# Driver.net
KiCad netlist of a schematic drawn in Altium Designer
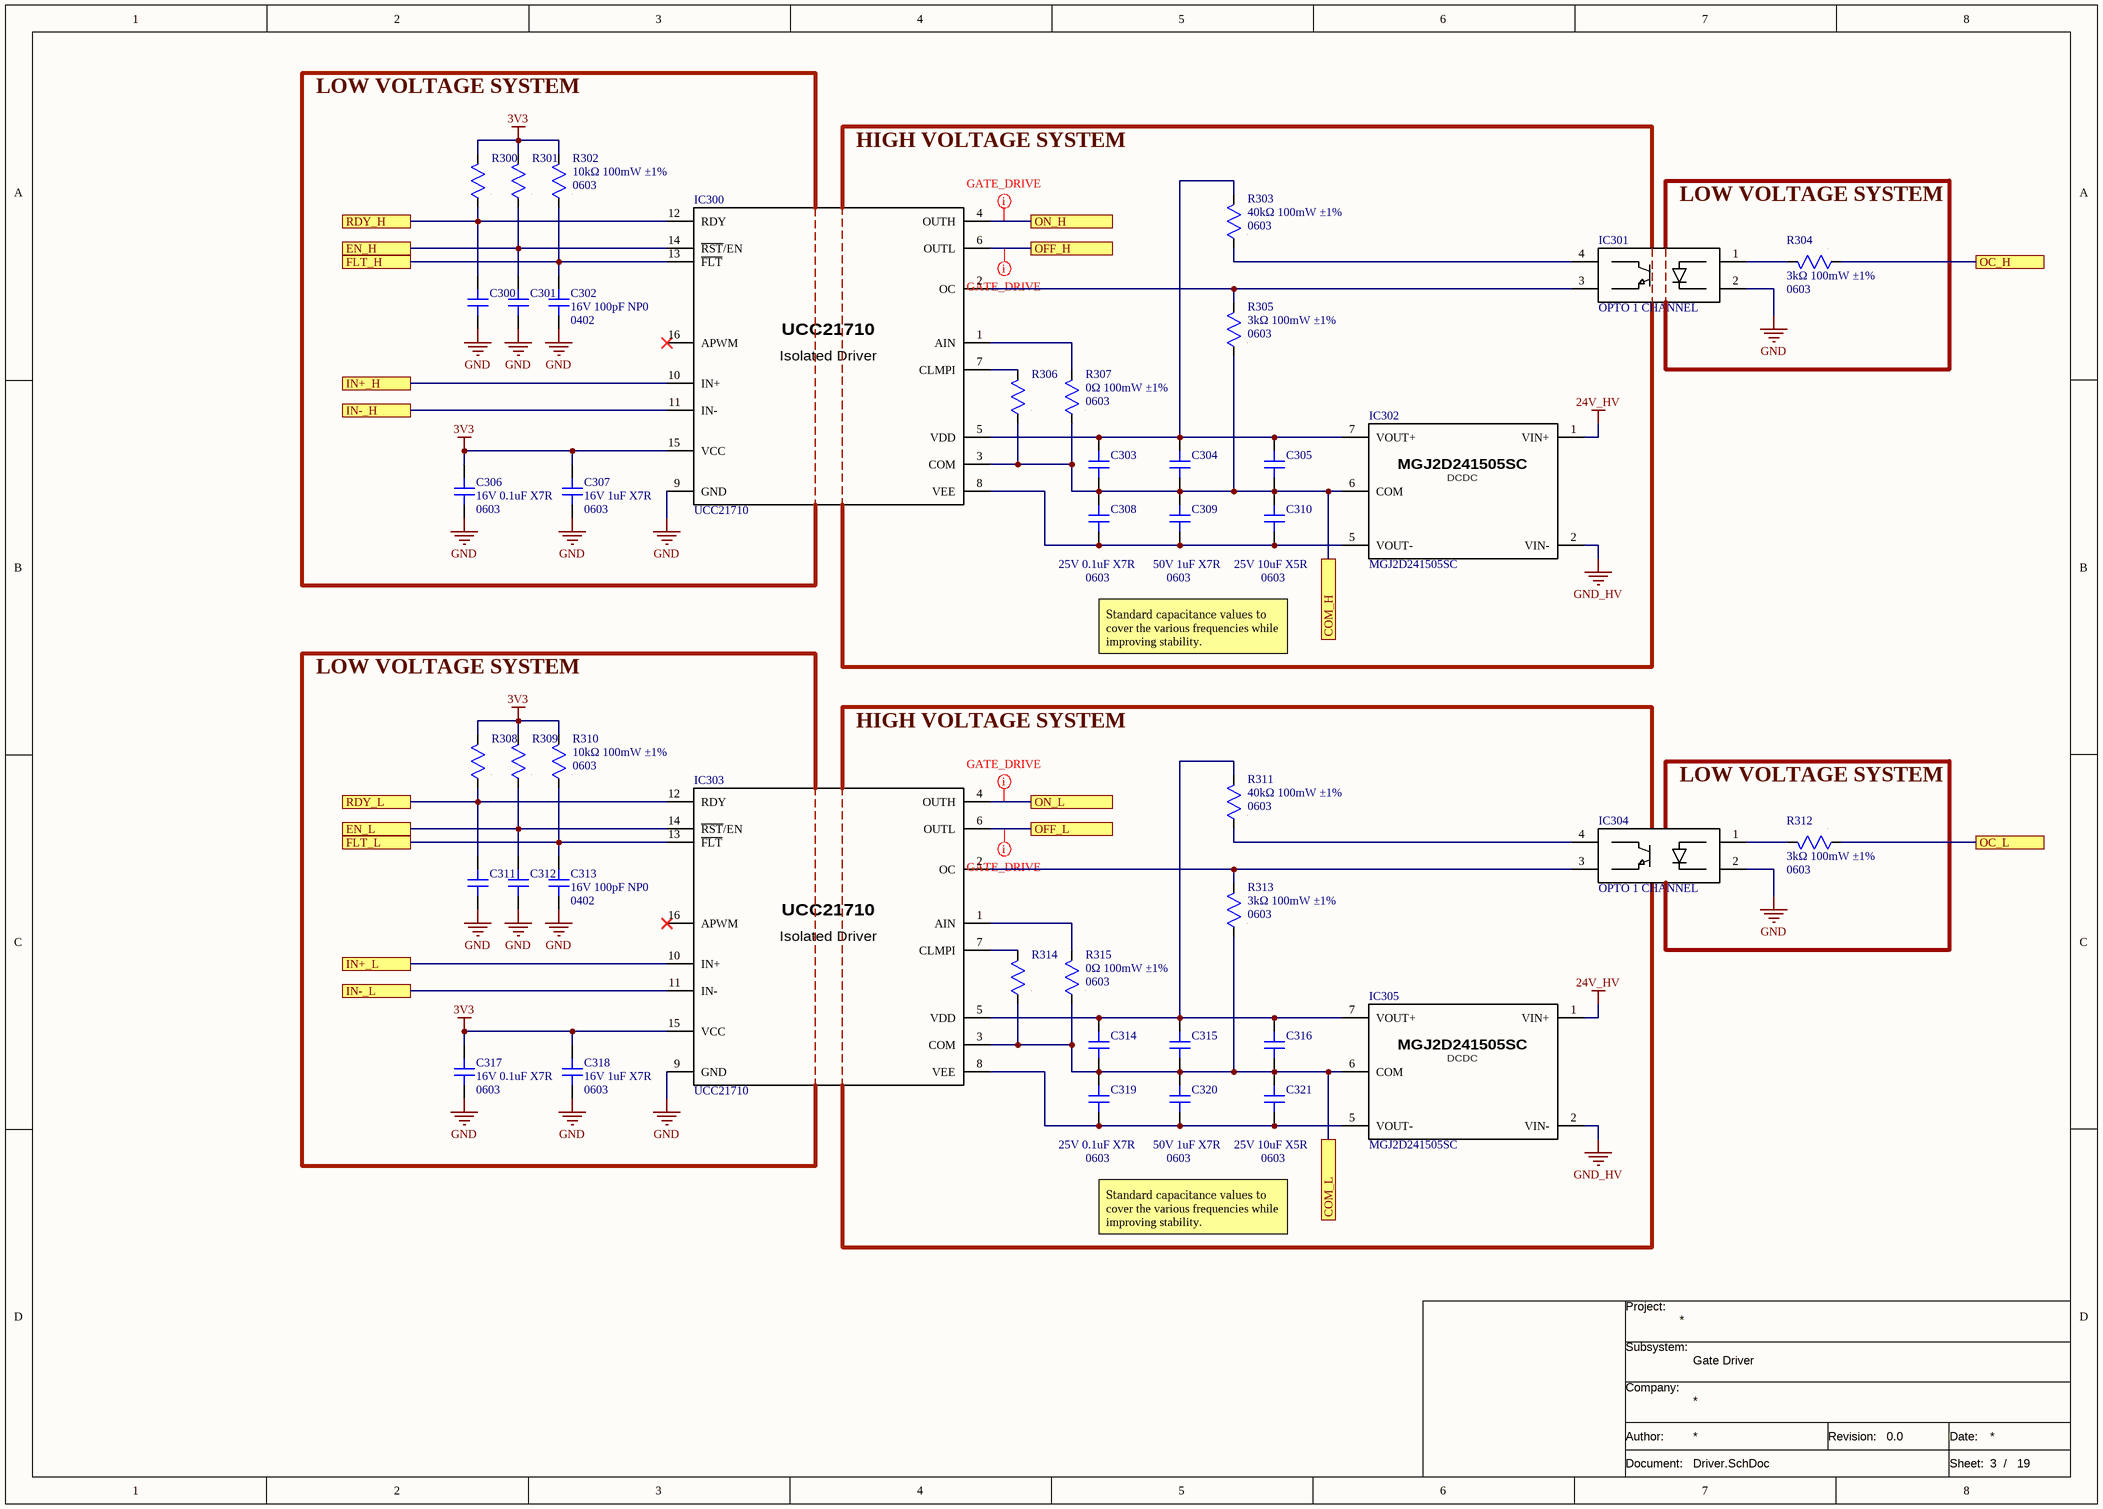
[diagram p0: Driver.SchDoc]

(export (version "E")
  (design (tool "Eeschema 10.0.6"))
  (components
    (comp (ref "C300")
      (value "CAP non polarized")
      (footprint "CAP SMD 0402")
      (description "Condensadores de cerámica multicapa (MLCC- SMD/SMT) WCAP-CSGP 100pF 0402 5% 16V MLCC")
      (fields (field (name "MPN") "885012005031") (field (name "MANUFACTURER") "Wurth Elektronik"))
      (libsource (lib "eUSR_Database") (part "CAP non polarized"))
    )
    (comp (ref "C301")
      (value "CAP non polarized")
      (footprint "CAP SMD 0402")
      (description "Condensadores de cerámica multicapa (MLCC- SMD/SMT) WCAP-CSGP 100pF 0402 5% 16V MLCC")
      (fields (field (name "MPN") "885012005031") (field (name "MANUFACTURER") "Wurth Elektronik"))
      (libsource (lib "eUSR_Database") (part "CAP non polarized"))
    )
    (comp (ref "C302")
      (value "16V 100pF NP0")
      (footprint "CAP SMD 0402")
      (description "Condensadores de cerámica multicapa (MLCC- SMD/SMT) WCAP-CSGP 100pF 0402 5% 16V MLCC")
      (fields
        (field (name "PACKAGE") "0402")
        (field (name "MPN") "885012005031")
        (field (name "MANUFACTURER") "Wurth Elektronik")
      )
      (libsource (lib "eUSR_Database") (part "CAP non polarized"))
    )
    (comp (ref "C303")
      (value "CAP non polarized")
      (footprint "CAP SMD 0603")
      (description "Condensadores de cerámica multicapa (MLCC- SMD/SMT) WCAP-CSGP 0.1uF 0603 10% 25V MLCC")
      (fields (field (name "MPN") "885012206071") (field (name "MANUFACTURER") "Wurth Elektronik"))
      (libsource (lib "eUSR_Database") (part "CAP non polarized"))
    )
    (comp (ref "C304")
      (value "CAP non polarized")
      (footprint "CAP SMD 0603")
      (description "Condensadores de cerámica multicapa (MLCC- SMD/SMT) WCAP-CSGP 1uF 50 Vol 10%")
      (fields (field (name "MPN") "885012206126") (field (name "MANUFACTURER") "Wurth Elektronik"))
      (libsource (lib "eUSR_Database") (part "CAP non polarized"))
    )
    (comp (ref "C305")
      (value "CAP non polarized")
      (footprint "CAP SMD 0603")
      (description "Condensadores de cerámica multicapa (MLCC- SMD/SMT) 0603 25VDC 10uF 10% X5R")
      (fields (field (name "MPN") "ZRB18AR61E106KE01L") (field (name "MANUFACTURER") "muRata"))
      (libsource (lib "eUSR_Database") (part "CAP non polarized"))
    )
    (comp (ref "C306")
      (value "16V 0.1uF X7R")
      (footprint "CAP SMD 0603")
      (description "Condensadores de cerámica multicapa (MLCC- SMD/SMT) WCAP-CSGP 0.1uF 0603 10% 16V MLCC")
      (fields
        (field (name "PACKAGE") "0603")
        (field (name "MPN") "885012206046")
        (field (name "MANUFACTURER") "Wurth Elektronik")
      )
      (libsource (lib "eUSR_Database") (part "CAP non polarized"))
    )
    (comp (ref "C307")
      (value "16V 1uF X7R")
      (footprint "CAP SMD 0603")
      (description "Condensadores de cerámica multicapa (MLCC- SMD/SMT) WCAP-CSGP 1uF 0603 10% 16V MLCC")
      (fields
        (field (name "PACKAGE") "0603")
        (field (name "MPN") "885012206052")
        (field (name "MANUFACTURER") "Wurth Elektronik")
      )
      (libsource (lib "eUSR_Database") (part "CAP non polarized"))
    )
    (comp (ref "C308")
      (value "25V 0.1uF X7R")
      (footprint "CAP SMD 0603")
      (description "Condensadores de cerámica multicapa (MLCC- SMD/SMT) WCAP-CSGP 0.1uF 0603 10% 25V MLCC")
      (fields
        (field (name "PACKAGE") "0603")
        (field (name "MPN") "885012206071")
        (field (name "MANUFACTURER") "Wurth Elektronik")
      )
      (libsource (lib "eUSR_Database") (part "CAP non polarized"))
    )
    (comp (ref "C309")
      (value "50V 1uF X7R")
      (footprint "CAP SMD 0603")
      (description "Condensadores de cerámica multicapa (MLCC- SMD/SMT) WCAP-CSGP 1uF 50 Vol 10%")
      (fields
        (field (name "PACKAGE") "0603")
        (field (name "MPN") "885012206126")
        (field (name "MANUFACTURER") "Wurth Elektronik")
      )
      (libsource (lib "eUSR_Database") (part "CAP non polarized"))
    )
    (comp (ref "C310")
      (value "25V 10uF X5R")
      (footprint "CAP SMD 0603")
      (description "Condensadores de cerámica multicapa (MLCC- SMD/SMT) 0603 25VDC 10uF 10% X5R")
      (fields
        (field (name "PACKAGE") "0603")
        (field (name "MPN") "ZRB18AR61E106KE01L")
        (field (name "MANUFACTURER") "muRata")
      )
      (libsource (lib "eUSR_Database") (part "CAP non polarized"))
    )
    (comp (ref "C311")
      (value "CAP non polarized")
      (footprint "CAP SMD 0402")
      (description "Condensadores de cerámica multicapa (MLCC- SMD/SMT) WCAP-CSGP 100pF 0402 5% 16V MLCC")
      (fields (field (name "MPN") "885012005031") (field (name "MANUFACTURER") "Wurth Elektronik"))
      (libsource (lib "eUSR_Database") (part "CAP non polarized"))
    )
    (comp (ref "C312")
      (value "CAP non polarized")
      (footprint "CAP SMD 0402")
      (description "Condensadores de cerámica multicapa (MLCC- SMD/SMT) WCAP-CSGP 100pF 0402 5% 16V MLCC")
      (fields (field (name "MPN") "885012005031") (field (name "MANUFACTURER") "Wurth Elektronik"))
      (libsource (lib "eUSR_Database") (part "CAP non polarized"))
    )
    (comp (ref "C313")
      (value "16V 100pF NP0")
      (footprint "CAP SMD 0402")
      (description "Condensadores de cerámica multicapa (MLCC- SMD/SMT) WCAP-CSGP 100pF 0402 5% 16V MLCC")
      (fields
        (field (name "PACKAGE") "0402")
        (field (name "MPN") "885012005031")
        (field (name "MANUFACTURER") "Wurth Elektronik")
      )
      (libsource (lib "eUSR_Database") (part "CAP non polarized"))
    )
    (comp (ref "C314")
      (value "CAP non polarized")
      (footprint "CAP SMD 0603")
      (description "Condensadores de cerámica multicapa (MLCC- SMD/SMT) WCAP-CSGP 0.1uF 0603 10% 25V MLCC")
      (fields (field (name "MPN") "885012206071") (field (name "MANUFACTURER") "Wurth Elektronik"))
      (libsource (lib "eUSR_Database") (part "CAP non polarized"))
    )
    (comp (ref "C315")
      (value "CAP non polarized")
      (footprint "CAP SMD 0603")
      (description "Condensadores de cerámica multicapa (MLCC- SMD/SMT) WCAP-CSGP 1uF 50 Vol 10%")
      (fields (field (name "MPN") "885012206126") (field (name "MANUFACTURER") "Wurth Elektronik"))
      (libsource (lib "eUSR_Database") (part "CAP non polarized"))
    )
    (comp (ref "C316")
      (value "CAP non polarized")
      (footprint "CAP SMD 0603")
      (description "Condensadores de cerámica multicapa (MLCC- SMD/SMT) 0603 25VDC 10uF 10% X5R")
      (fields (field (name "MPN") "ZRB18AR61E106KE01L") (field (name "MANUFACTURER") "muRata"))
      (libsource (lib "eUSR_Database") (part "CAP non polarized"))
    )
    (comp (ref "C317")
      (value "16V 0.1uF X7R")
      (footprint "CAP SMD 0603")
      (description "Condensadores de cerámica multicapa (MLCC- SMD/SMT) WCAP-CSGP 0.1uF 0603 10% 16V MLCC")
      (fields
        (field (name "PACKAGE") "0603")
        (field (name "MPN") "885012206046")
        (field (name "MANUFACTURER") "Wurth Elektronik")
      )
      (libsource (lib "eUSR_Database") (part "CAP non polarized"))
    )
    (comp (ref "C318")
      (value "16V 1uF X7R")
      (footprint "CAP SMD 0603")
      (description "Condensadores de cerámica multicapa (MLCC- SMD/SMT) WCAP-CSGP 1uF 0603 10% 16V MLCC")
      (fields
        (field (name "PACKAGE") "0603")
        (field (name "MPN") "885012206052")
        (field (name "MANUFACTURER") "Wurth Elektronik")
      )
      (libsource (lib "eUSR_Database") (part "CAP non polarized"))
    )
    (comp (ref "C319")
      (value "25V 0.1uF X7R")
      (footprint "CAP SMD 0603")
      (description "Condensadores de cerámica multicapa (MLCC- SMD/SMT) WCAP-CSGP 0.1uF 0603 10% 25V MLCC")
      (fields
        (field (name "PACKAGE") "0603")
        (field (name "MPN") "885012206071")
        (field (name "MANUFACTURER") "Wurth Elektronik")
      )
      (libsource (lib "eUSR_Database") (part "CAP non polarized"))
    )
    (comp (ref "C320")
      (value "50V 1uF X7R")
      (footprint "CAP SMD 0603")
      (description "Condensadores de cerámica multicapa (MLCC- SMD/SMT) WCAP-CSGP 1uF 50 Vol 10%")
      (fields
        (field (name "PACKAGE") "0603")
        (field (name "MPN") "885012206126")
        (field (name "MANUFACTURER") "Wurth Elektronik")
      )
      (libsource (lib "eUSR_Database") (part "CAP non polarized"))
    )
    (comp (ref "C321")
      (value "25V 10uF X5R")
      (footprint "CAP SMD 0603")
      (description "Condensadores de cerámica multicapa (MLCC- SMD/SMT) 0603 25VDC 10uF 10% X5R")
      (fields
        (field (name "PACKAGE") "0603")
        (field (name "MPN") "ZRB18AR61E106KE01L")
        (field (name "MANUFACTURER") "muRata")
      )
      (libsource (lib "eUSR_Database") (part "CAP non polarized"))
    )
    (comp (ref "IC300")
      (value "UCC21710")
      (footprint "SOIC-16")
      (fields (field (name "MPN") "UCC21710QDWRQ1") (field (name "MANUFACTURER") "Texas Instruments"))
      (libsource (lib "eUSR_Database") (part "UCC21710"))
    )
    (comp (ref "IC301")
      (value "OPTO 1 CHANNEL")
      (footprint "SOIC-4")
      (description "Optoacopladores para salidas de transistores Automotive DC-input transistor-output s")
      (fields (field (name "MPN") "ISOM8110DFHRQ1") (field (name "MANUFACTURER") "Texas Instruments"))
      (libsource (lib "eUSR_Database") (part "OPTO 1 CHANNEL"))
    )
    (comp (ref "IC302")
      (value "MGJ2D241505SC")
      (footprint "MGJ2D241505SC")
      (description "Convertidores DC/DC para montaje pasante 2W 24-15VIN 5VOUT DC/DC")
      (fields (field (name "MANUFACTURER") "Murata Power Solutions"))
      (libsource (lib "eUSR_Database") (part "MGJ2D241505SC"))
    )
    (comp (ref "IC303")
      (value "UCC21710")
      (footprint "SOIC-16")
      (fields (field (name "MPN") "UCC21710QDWRQ1") (field (name "MANUFACTURER") "Texas Instruments"))
      (libsource (lib "eUSR_Database") (part "UCC21710"))
    )
    (comp (ref "IC304")
      (value "OPTO 1 CHANNEL")
      (footprint "SOIC-4")
      (description "Optoacopladores para salidas de transistores Automotive DC-input transistor-output s")
      (fields (field (name "MPN") "ISOM8110DFHRQ1") (field (name "MANUFACTURER") "Texas Instruments"))
      (libsource (lib "eUSR_Database") (part "OPTO 1 CHANNEL"))
    )
    (comp (ref "IC305")
      (value "MGJ2D241505SC")
      (footprint "MGJ2D241505SC")
      (description "Convertidores DC/DC para montaje pasante 2W 24-15VIN 5VOUT DC/DC")
      (fields (field (name "MANUFACTURER") "Murata Power Solutions"))
      (libsource (lib "eUSR_Database") (part "MGJ2D241505SC"))
    )
    (comp (ref "R300")
      (value "RES")
      (footprint "RES SMD 0603")
      (description "Resistores de película gruesa - SMD WRIS-RSKS 10 kOhms 1 % 0.1 W 0603 AEC-Q200")
      (fields (field (name "MPN") "560112116005") (field (name "MANUFACTURER") "Wurth Elektronik"))
      (libsource (lib "eUSR_Database") (part "RES"))
    )
    (comp (ref "R301")
      (value "RES")
      (footprint "RES SMD 0603")
      (description "Resistores de película gruesa - SMD WRIS-RSKS 10 kOhms 1 % 0.1 W 0603 AEC-Q200")
      (fields (field (name "MPN") "560112116005") (field (name "MANUFACTURER") "Wurth Elektronik"))
      (libsource (lib "eUSR_Database") (part "RES"))
    )
    (comp (ref "R302")
      (value "10kΩ 100mW ±1%")
      (footprint "RES SMD 0603")
      (description "Resistores de película gruesa - SMD WRIS-RSKS 10 kOhms 1 % 0.1 W 0603 AEC-Q200")
      (fields
        (field (name "PACKAGE") "0603")
        (field (name "MPN") "560112116005")
        (field (name "MANUFACTURER") "Wurth Elektronik")
      )
      (libsource (lib "eUSR_Database") (part "RES"))
    )
    (comp (ref "R303")
      (value "40kΩ 100mW ±1%")
      (footprint "RES SMD 0603")
      (description "Thin Film Resistors 40kOhm 1/10W 0603 .1 %")
      (fields
        (field (name "PACKAGE") "0603")
        (field (name "MPN") "RT0603BRD0740KL")
        (field (name "MANUFACTURER") "YAGEO")
      )
      (libsource (lib "eUSR_Database") (part "RES"))
    )
    (comp (ref "R304")
      (value "3kΩ 100mW ±1%")
      (footprint "RES SMD 0603")
      (description "Thin Film Resistors .1W 3Kohm 1% 0603 50ppm Auto")
      (fields
        (field (name "PACKAGE") "0603")
        (field (name "MPN") "MCT06030C3001FP500")
        (field (name "MANUFACTURER") "Vishay")
      )
      (libsource (lib "eUSR_Database") (part "RES"))
    )
    (comp (ref "R305")
      (value "3kΩ 100mW ±1%")
      (footprint "RES SMD 0603")
      (description "Thin Film Resistors .1W 3Kohm 1% 0603 50ppm Auto")
      (fields
        (field (name "PACKAGE") "0603")
        (field (name "MPN") "MCT06030C3001FP500")
        (field (name "MANUFACTURER") "Vishay")
      )
      (libsource (lib "eUSR_Database") (part "RES"))
    )
    (comp (ref "R306")
      (value "RES")
      (footprint "RES SMD 0603")
      (description "Resistores de película gruesa - SMD WRIS-RSKS <0.05 Ohms 0.1 W Jumper 0603 AEC-Q200")
      (fields (field (name "MPN") "5,60112116e+11") (field (name "MANUFACTURER") "Wurth Elektronik"))
      (libsource (lib "eUSR_Database") (part "RES"))
    )
    (comp (ref "R307")
      (value "0Ω 100mW ±1%")
      (footprint "RES SMD 0603")
      (description "Resistores de película gruesa - SMD WRIS-RSKS <0.05 Ohms 0.1 W Jumper 0603 AEC-Q200")
      (fields
        (field (name "PACKAGE") "0603")
        (field (name "MPN") "5,60112116e+11")
        (field (name "MANUFACTURER") "Wurth Elektronik")
      )
      (libsource (lib "eUSR_Database") (part "RES"))
    )
    (comp (ref "R308")
      (value "RES")
      (footprint "RES SMD 0603")
      (description "Resistores de película gruesa - SMD WRIS-RSKS 10 kOhms 1 % 0.1 W 0603 AEC-Q200")
      (fields (field (name "MPN") "560112116005") (field (name "MANUFACTURER") "Wurth Elektronik"))
      (libsource (lib "eUSR_Database") (part "RES"))
    )
    (comp (ref "R309")
      (value "RES")
      (footprint "RES SMD 0603")
      (description "Resistores de película gruesa - SMD WRIS-RSKS 10 kOhms 1 % 0.1 W 0603 AEC-Q200")
      (fields (field (name "MPN") "560112116005") (field (name "MANUFACTURER") "Wurth Elektronik"))
      (libsource (lib "eUSR_Database") (part "RES"))
    )
    (comp (ref "R310")
      (value "10kΩ 100mW ±1%")
      (footprint "RES SMD 0603")
      (description "Resistores de película gruesa - SMD WRIS-RSKS 10 kOhms 1 % 0.1 W 0603 AEC-Q200")
      (fields
        (field (name "PACKAGE") "0603")
        (field (name "MPN") "560112116005")
        (field (name "MANUFACTURER") "Wurth Elektronik")
      )
      (libsource (lib "eUSR_Database") (part "RES"))
    )
    (comp (ref "R311")
      (value "40kΩ 100mW ±1%")
      (footprint "RES SMD 0603")
      (description "Thin Film Resistors 40kOhm 1/10W 0603 .1 %")
      (fields
        (field (name "PACKAGE") "0603")
        (field (name "MPN") "RT0603BRD0740KL")
        (field (name "MANUFACTURER") "YAGEO")
      )
      (libsource (lib "eUSR_Database") (part "RES"))
    )
    (comp (ref "R312")
      (value "3kΩ 100mW ±1%")
      (footprint "RES SMD 0603")
      (description "Thin Film Resistors .1W 3Kohm 1% 0603 50ppm Auto")
      (fields
        (field (name "PACKAGE") "0603")
        (field (name "MPN") "MCT06030C3001FP500")
        (field (name "MANUFACTURER") "Vishay")
      )
      (libsource (lib "eUSR_Database") (part "RES"))
    )
    (comp (ref "R313")
      (value "3kΩ 100mW ±1%")
      (footprint "RES SMD 0603")
      (description "Thin Film Resistors .1W 3Kohm 1% 0603 50ppm Auto")
      (fields
        (field (name "PACKAGE") "0603")
        (field (name "MPN") "MCT06030C3001FP500")
        (field (name "MANUFACTURER") "Vishay")
      )
      (libsource (lib "eUSR_Database") (part "RES"))
    )
    (comp (ref "R314")
      (value "RES")
      (footprint "RES SMD 0603")
      (description "Resistores de película gruesa - SMD WRIS-RSKS <0.05 Ohms 0.1 W Jumper 0603 AEC-Q200")
      (fields (field (name "MPN") "5,60112116e+11") (field (name "MANUFACTURER") "Wurth Elektronik"))
      (libsource (lib "eUSR_Database") (part "RES"))
    )
    (comp (ref "R315")
      (value "0Ω 100mW ±1%")
      (footprint "RES SMD 0603")
      (description "Resistores de película gruesa - SMD WRIS-RSKS <0.05 Ohms 0.1 W Jumper 0603 AEC-Q200")
      (fields
        (field (name "PACKAGE") "0603")
        (field (name "MPN") "5,60112116e+11")
        (field (name "MANUFACTURER") "Wurth Elektronik")
      )
      (libsource (lib "eUSR_Database") (part "RES"))
    )
  )
  (nets
    (net (code "1") (name "/COM_H") (class "Default")
      (node (ref "C303") (pin "2") (pinfunction "2_2") (pintype "passive"))
      (node (ref "C304") (pin "2") (pinfunction "2_2") (pintype "passive"))
      (node (ref "C305") (pin "2") (pinfunction "2_2") (pintype "passive"))
      (node (ref "C308") (pin "1") (pinfunction "1_1") (pintype "passive"))
      (node (ref "C309") (pin "1") (pinfunction "1_1") (pintype "passive"))
      (node (ref "C310") (pin "1") (pinfunction "1_1") (pintype "passive"))
      (node (ref "IC300") (pin "3") (pinfunction "COM_3") (pintype "passive"))
      (node (ref "IC302") (pin "6") (pinfunction "COM_6") (pintype "passive"))
      (node (ref "R305") (pin "1") (pinfunction "1_1") (pintype "passive"))
      (node (ref "R306") (pin "1") (pinfunction "1_1") (pintype "passive"))
      (node (ref "R307") (pin "1") (pinfunction "1_1") (pintype "passive"))
    )
    (net (code "2") (name "/COM_L") (class "Default")
      (node (ref "C314") (pin "2") (pinfunction "2_2") (pintype "passive"))
      (node (ref "C315") (pin "2") (pinfunction "2_2") (pintype "passive"))
      (node (ref "C316") (pin "2") (pinfunction "2_2") (pintype "passive"))
      (node (ref "C319") (pin "1") (pinfunction "1_1") (pintype "passive"))
      (node (ref "C320") (pin "1") (pinfunction "1_1") (pintype "passive"))
      (node (ref "C321") (pin "1") (pinfunction "1_1") (pintype "passive"))
      (node (ref "IC303") (pin "3") (pinfunction "COM_3") (pintype "passive"))
      (node (ref "IC305") (pin "6") (pinfunction "COM_6") (pintype "passive"))
      (node (ref "R313") (pin "1") (pinfunction "1_1") (pintype "passive"))
      (node (ref "R314") (pin "1") (pinfunction "1_1") (pintype "passive"))
      (node (ref "R315") (pin "1") (pinfunction "1_1") (pintype "passive"))
    )
    (net (code "3") (name "/EN_H") (class "Default")
      (node (ref "C301") (pin "1") (pinfunction "1_1") (pintype "passive"))
      (node (ref "IC300") (pin "14") (pinfunction "~{RST}/EN_14") (pintype "passive"))
      (node (ref "R301") (pin "1") (pinfunction "1_1") (pintype "passive"))
    )
    (net (code "4") (name "/EN_L") (class "Default")
      (node (ref "C312") (pin "1") (pinfunction "1_1") (pintype "passive"))
      (node (ref "IC303") (pin "14") (pinfunction "~{RST}/EN_14") (pintype "passive"))
      (node (ref "R309") (pin "1") (pinfunction "1_1") (pintype "passive"))
    )
    (net (code "5") (name "/FLT_H") (class "Default")
      (node (ref "C302") (pin "1") (pinfunction "1_1") (pintype "passive"))
      (node (ref "IC300") (pin "13") (pinfunction "~{FLT}_13") (pintype "passive"))
      (node (ref "R302") (pin "1") (pinfunction "1_1") (pintype "passive"))
    )
    (net (code "6") (name "/FLT_L") (class "Default")
      (node (ref "C313") (pin "1") (pinfunction "1_1") (pintype "passive"))
      (node (ref "IC303") (pin "13") (pinfunction "~{FLT}_13") (pintype "passive"))
      (node (ref "R310") (pin "1") (pinfunction "1_1") (pintype "passive"))
    )
    (net (code "7") (name "/IN+_H") (class "Default")
      (node (ref "IC300") (pin "10") (pinfunction "IN+_10") (pintype "passive"))
    )
    (net (code "8") (name "/IN+_L") (class "Default")
      (node (ref "IC303") (pin "10") (pinfunction "IN+_10") (pintype "passive"))
    )
    (net (code "9") (name "/IN-_H") (class "Default")
      (node (ref "IC300") (pin "11") (pinfunction "IN-_11") (pintype "passive"))
    )
    (net (code "10") (name "/IN-_L") (class "Default")
      (node (ref "IC303") (pin "11") (pinfunction "IN-_11") (pintype "passive"))
    )
    (net (code "11") (name "/OC_H") (class "Default")
      (node (ref "R304") (pin "1") (pinfunction "1_1") (pintype "passive"))
    )
    (net (code "12") (name "/OC_L") (class "Default")
      (node (ref "R312") (pin "1") (pinfunction "1_1") (pintype "passive"))
    )
    (net (code "13") (name "/OFF_H") (class "Default")
      (node (ref "IC300") (pin "6") (pinfunction "OUTL_6") (pintype "passive"))
    )
    (net (code "14") (name "/OFF_L") (class "Default")
      (node (ref "IC303") (pin "6") (pinfunction "OUTL_6") (pintype "passive"))
    )
    (net (code "15") (name "/ON_H") (class "Default")
      (node (ref "IC300") (pin "4") (pinfunction "OUTH_4") (pintype "passive"))
    )
    (net (code "16") (name "/ON_L") (class "Default")
      (node (ref "IC303") (pin "4") (pinfunction "OUTH_4") (pintype "passive"))
    )
    (net (code "17") (name "/RDY_H") (class "Default")
      (node (ref "C300") (pin "1") (pinfunction "1_1") (pintype "passive"))
      (node (ref "IC300") (pin "12") (pinfunction "RDY_12") (pintype "passive"))
      (node (ref "R300") (pin "1") (pinfunction "1_1") (pintype "passive"))
    )
    (net (code "18") (name "/RDY_L") (class "Default")
      (node (ref "C311") (pin "1") (pinfunction "1_1") (pintype "passive"))
      (node (ref "IC303") (pin "12") (pinfunction "RDY_12") (pintype "passive"))
      (node (ref "R308") (pin "1") (pinfunction "1_1") (pintype "passive"))
    )
    (net (code "19") (name "3V3") (class "Default")
      (node (ref "C306") (pin "1") (pinfunction "1_1") (pintype "passive"))
      (node (ref "C307") (pin "1") (pinfunction "1_1") (pintype "passive"))
      (node (ref "C317") (pin "1") (pinfunction "1_1") (pintype "passive"))
      (node (ref "C318") (pin "1") (pinfunction "1_1") (pintype "passive"))
      (node (ref "IC300") (pin "15") (pinfunction "VCC_15") (pintype "power_in"))
      (node (ref "IC303") (pin "15") (pinfunction "VCC_15") (pintype "power_in"))
      (node (ref "R300") (pin "2") (pinfunction "2_2") (pintype "passive"))
      (node (ref "R301") (pin "2") (pinfunction "2_2") (pintype "passive"))
      (node (ref "R302") (pin "2") (pinfunction "2_2") (pintype "passive"))
      (node (ref "R308") (pin "2") (pinfunction "2_2") (pintype "passive"))
      (node (ref "R309") (pin "2") (pinfunction "2_2") (pintype "passive"))
      (node (ref "R310") (pin "2") (pinfunction "2_2") (pintype "passive"))
    )
    (net (code "20") (name "24V_HV") (class "Default")
      (node (ref "IC302") (pin "1") (pinfunction "VIN+_1") (pintype "passive"))
      (node (ref "IC305") (pin "1") (pinfunction "VIN+_1") (pintype "passive"))
    )
    (net (code "21") (name "GND") (class "Default")
      (node (ref "C300") (pin "2") (pinfunction "2_2") (pintype "passive"))
      (node (ref "C301") (pin "2") (pinfunction "2_2") (pintype "passive"))
      (node (ref "C302") (pin "2") (pinfunction "2_2") (pintype "passive"))
      (node (ref "C306") (pin "2") (pinfunction "2_2") (pintype "passive"))
      (node (ref "C307") (pin "2") (pinfunction "2_2") (pintype "passive"))
      (node (ref "C311") (pin "2") (pinfunction "2_2") (pintype "passive"))
      (node (ref "C312") (pin "2") (pinfunction "2_2") (pintype "passive"))
      (node (ref "C313") (pin "2") (pinfunction "2_2") (pintype "passive"))
      (node (ref "C317") (pin "2") (pinfunction "2_2") (pintype "passive"))
      (node (ref "C318") (pin "2") (pinfunction "2_2") (pintype "passive"))
      (node (ref "IC300") (pin "9") (pinfunction "GND_9") (pintype "power_in"))
      (node (ref "IC301") (pin "2") (pinfunction "K_1_2") (pintype "passive"))
      (node (ref "IC303") (pin "9") (pinfunction "GND_9") (pintype "power_in"))
      (node (ref "IC304") (pin "2") (pinfunction "K_1_2") (pintype "passive"))
    )
    (net (code "22") (name "GND_HV") (class "Default")
      (node (ref "IC302") (pin "2") (pinfunction "VIN-_2") (pintype "passive"))
      (node (ref "IC305") (pin "2") (pinfunction "VIN-_2") (pintype "passive"))
    )
    (net (code "23") (name "Net-(IC300-AIN)") (class "Default")
      (node (ref "IC300") (pin "1") (pinfunction "AIN_1") (pintype "passive"))
      (node (ref "R307") (pin "2") (pinfunction "2_2") (pintype "passive"))
    )
    (net (code "24") (name "Net-(IC300-CLMPI)") (class "Default")
      (node (ref "IC300") (pin "7") (pinfunction "CLMPI_7") (pintype "passive"))
      (node (ref "R306") (pin "2") (pinfunction "2_2") (pintype "passive"))
    )
    (net (code "25") (name "Net-(IC300-OC)") (class "Default")
      (node (ref "IC300") (pin "2") (pinfunction "OC_2") (pintype "passive"))
      (node (ref "IC301") (pin "3") (pinfunction "E_1_3") (pintype "passive"))
      (node (ref "R305") (pin "2") (pinfunction "2_2") (pintype "passive"))
    )
    (net (code "26") (name "Net-(IC300-VDD)") (class "Default")
      (node (ref "C303") (pin "1") (pinfunction "1_1") (pintype "passive"))
      (node (ref "C304") (pin "1") (pinfunction "1_1") (pintype "passive"))
      (node (ref "C305") (pin "1") (pinfunction "1_1") (pintype "passive"))
      (node (ref "IC300") (pin "5") (pinfunction "VDD_5") (pintype "power_in"))
      (node (ref "IC302") (pin "7") (pinfunction "VOUT+_7") (pintype "passive"))
      (node (ref "R303") (pin "2") (pinfunction "2_2") (pintype "passive"))
    )
    (net (code "27") (name "Net-(IC300-VEE)") (class "Default")
      (node (ref "C308") (pin "2") (pinfunction "2_2") (pintype "passive"))
      (node (ref "C309") (pin "2") (pinfunction "2_2") (pintype "passive"))
      (node (ref "C310") (pin "2") (pinfunction "2_2") (pintype "passive"))
      (node (ref "IC300") (pin "8") (pinfunction "VEE_8") (pintype "passive"))
      (node (ref "IC302") (pin "5") (pinfunction "VOUT-_5") (pintype "passive"))
    )
    (net (code "28") (name "Net-(IC301-A_1)") (class "Default")
      (node (ref "IC301") (pin "1") (pinfunction "A_1_1") (pintype "passive"))
      (node (ref "R304") (pin "2") (pinfunction "2_2") (pintype "passive"))
    )
    (net (code "29") (name "Net-(IC301-C_1)") (class "Default")
      (node (ref "IC301") (pin "4") (pinfunction "C_1_4") (pintype "passive"))
      (node (ref "R303") (pin "1") (pinfunction "1_1") (pintype "passive"))
    )
    (net (code "30") (name "Net-(IC303-AIN)") (class "Default")
      (node (ref "IC303") (pin "1") (pinfunction "AIN_1") (pintype "passive"))
      (node (ref "R315") (pin "2") (pinfunction "2_2") (pintype "passive"))
    )
    (net (code "31") (name "Net-(IC303-CLMPI)") (class "Default")
      (node (ref "IC303") (pin "7") (pinfunction "CLMPI_7") (pintype "passive"))
      (node (ref "R314") (pin "2") (pinfunction "2_2") (pintype "passive"))
    )
    (net (code "32") (name "Net-(IC303-OC)") (class "Default")
      (node (ref "IC303") (pin "2") (pinfunction "OC_2") (pintype "passive"))
      (node (ref "IC304") (pin "3") (pinfunction "E_1_3") (pintype "passive"))
      (node (ref "R313") (pin "2") (pinfunction "2_2") (pintype "passive"))
    )
    (net (code "33") (name "Net-(IC303-VDD)") (class "Default")
      (node (ref "C314") (pin "1") (pinfunction "1_1") (pintype "passive"))
      (node (ref "C315") (pin "1") (pinfunction "1_1") (pintype "passive"))
      (node (ref "C316") (pin "1") (pinfunction "1_1") (pintype "passive"))
      (node (ref "IC303") (pin "5") (pinfunction "VDD_5") (pintype "power_in"))
      (node (ref "IC305") (pin "7") (pinfunction "VOUT+_7") (pintype "passive"))
      (node (ref "R311") (pin "2") (pinfunction "2_2") (pintype "passive"))
    )
    (net (code "34") (name "Net-(IC303-VEE)") (class "Default")
      (node (ref "C319") (pin "2") (pinfunction "2_2") (pintype "passive"))
      (node (ref "C320") (pin "2") (pinfunction "2_2") (pintype "passive"))
      (node (ref "C321") (pin "2") (pinfunction "2_2") (pintype "passive"))
      (node (ref "IC303") (pin "8") (pinfunction "VEE_8") (pintype "passive"))
      (node (ref "IC305") (pin "5") (pinfunction "VOUT-_5") (pintype "passive"))
    )
    (net (code "35") (name "Net-(IC304-A_1)") (class "Default")
      (node (ref "IC304") (pin "1") (pinfunction "A_1_1") (pintype "passive"))
      (node (ref "R312") (pin "2") (pinfunction "2_2") (pintype "passive"))
    )
    (net (code "36") (name "Net-(IC304-C_1)") (class "Default")
      (node (ref "IC304") (pin "4") (pinfunction "C_1_4") (pintype "passive"))
      (node (ref "R311") (pin "1") (pinfunction "1_1") (pintype "passive"))
    )
    (net (code "37") (name "unconnected-(IC300-APWM-Pad16)") (class "Default")
      (node (ref "IC300") (pin "16") (pinfunction "APWM_16") (pintype "passive+no_connect"))
    )
    (net (code "38") (name "unconnected-(IC303-APWM-Pad16)") (class "Default")
      (node (ref "IC303") (pin "16") (pinfunction "APWM_16") (pintype "passive+no_connect"))
    )
  )
)
